# Linear_Power_Supply_5V.net
KiCad netlist of a schematic drawn in EAGLE
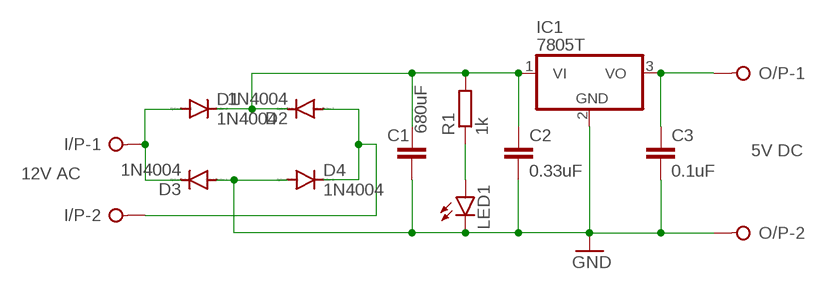
[diagram p0: schematic, sheet 1]

(export (version "E")
  (design (tool "Eeschema 10.0.6"))
  (components
    (comp (ref "C1")
      (value "680uF")
      (footprint "eagle-import:C025-060X050")
      (libsource (lib "eagle-import") (part "C-EU025-060X050"))
    )
    (comp (ref "C2")
      (value "0.33uF")
      (footprint "eagle-import:C025-060X050")
      (libsource (lib "eagle-import") (part "C-EU025-060X050"))
    )
    (comp (ref "C3")
      (value "0.1uF")
      (footprint "eagle-import:C025-060X050")
      (libsource (lib "eagle-import") (part "C-EU025-060X050"))
    )
    (comp (ref "D1")
      (value "1N4004")
      (footprint "eagle-import:DO41-10")
      (libsource (lib "eagle-import") (part "1N4004"))
    )
    (comp (ref "D2")
      (value "1N4004")
      (footprint "eagle-import:DO41-10")
      (libsource (lib "eagle-import") (part "1N4004"))
    )
    (comp (ref "D3")
      (value "1N4004")
      (footprint "eagle-import:DO41-10")
      (libsource (lib "eagle-import") (part "1N4004"))
    )
    (comp (ref "D4")
      (value "1N4004")
      (footprint "eagle-import:DO41-10")
      (libsource (lib "eagle-import") (part "1N4004"))
    )
    (comp (ref "I/P")
      (value "12V AC")
      (footprint "eagle-import:W237-132")
      (libsource (lib "eagle-import") (part "W237-02P"))
    )
    (comp (ref "IC1")
      (value "7805T")
      (footprint "eagle-import:TO220H")
      (libsource (lib "eagle-import") (part "78T05"))
    )
    (comp (ref "LED1")
      (value "LED3MM")
      (footprint "eagle-import:LED3MM")
      (libsource (lib "eagle-import") (part "LED3MM"))
    )
    (comp (ref "O/P")
      (value "5V DC")
      (footprint "eagle-import:W237-132")
      (libsource (lib "eagle-import") (part "W237-02P"))
    )
    (comp (ref "R1")
      (value "1k")
      (footprint "eagle-import:0207_12")
      (libsource (lib "eagle-import") (part "R-EU_0207/12"))
    )
  )
  (nets
    (net (code "1") (name "GND") (class "Default")
      (node (ref "C1") (pin "2") (pinfunction "2_2") (pintype "passive"))
      (node (ref "C2") (pin "2") (pinfunction "2_2") (pintype "passive"))
      (node (ref "C3") (pin "2") (pinfunction "2_2") (pintype "passive"))
      (node (ref "D3") (pin "A") (pinfunction "A_A") (pintype "passive"))
      (node (ref "D4") (pin "A") (pinfunction "A_A") (pintype "passive"))
      (node (ref "IC1") (pin "2") (pinfunction "GND_2") (pintype "passive"))
      (node (ref "LED1") (pin "K") (pinfunction "C_K") (pintype "passive"))
      (node (ref "O/P") (pin "2") (pinfunction "KL_2") (pintype "passive"))
    )
    (net (code "2") (name "Net-(I/PA-KL)") (class "Default")
      (node (ref "D1") (pin "A") (pinfunction "A_A") (pintype "passive"))
      (node (ref "D3") (pin "C") (pinfunction "C_C") (pintype "passive"))
      (node (ref "I/P") (pin "1") (pinfunction "KL_1") (pintype "passive"))
    )
    (net (code "3") (name "Net-(I/PB-KL)") (class "Default")
      (node (ref "D2") (pin "A") (pinfunction "A_A") (pintype "passive"))
      (node (ref "D4") (pin "C") (pinfunction "C_C") (pintype "passive"))
      (node (ref "I/P") (pin "2") (pinfunction "KL_2") (pintype "passive"))
    )
    (net (code "4") (name "Net-(IC1-VI)") (class "Default")
      (node (ref "C1") (pin "1") (pinfunction "1_1") (pintype "passive"))
      (node (ref "C2") (pin "1") (pinfunction "1_1") (pintype "passive"))
      (node (ref "D1") (pin "C") (pinfunction "C_C") (pintype "passive"))
      (node (ref "D2") (pin "C") (pinfunction "C_C") (pintype "passive"))
      (node (ref "IC1") (pin "1") (pinfunction "VI_1") (pintype "input"))
      (node (ref "R1") (pin "2") (pinfunction "2_2") (pintype "passive"))
    )
    (net (code "5") (name "Net-(IC1-VO)") (class "Default")
      (node (ref "C3") (pin "1") (pinfunction "1_1") (pintype "passive"))
      (node (ref "IC1") (pin "3") (pinfunction "VO_3") (pintype "passive"))
      (node (ref "O/P") (pin "1") (pinfunction "KL_1") (pintype "passive"))
    )
    (net (code "6") (name "Net-(LED1-PadA)") (class "Default")
      (node (ref "LED1") (pin "A") (pinfunction "A_A") (pintype "passive"))
      (node (ref "R1") (pin "1") (pinfunction "1_1") (pintype "passive"))
    )
  )
)
